# OSC_V1.net
KiCad netlist of a schematic drawn in EAGLE
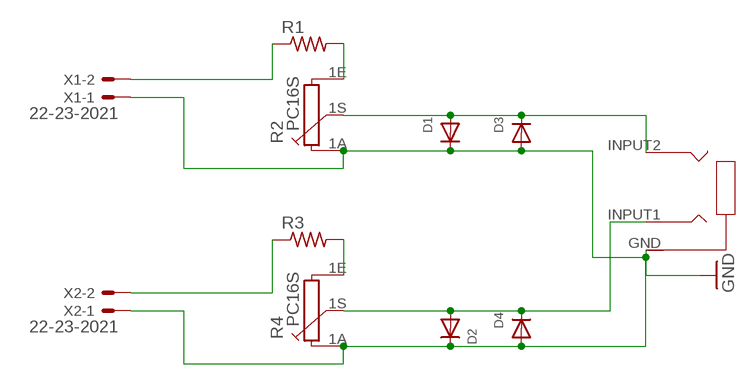
[diagram p0: schematic, sheet 1]

(export (version "E")
  (design (tool "Eeschema 10.0.6"))
  (components
    (comp (ref "D1")
      (value "DIODEDO-1N4148")
      (footprint "eagle-import:DO-1N4148")
      (fields (field (name "MPN") "1N4148 (DO-35)"))
      (libsource (lib "eagle-import") (part "DIODEDO-1N4148"))
    )
    (comp (ref "D2")
      (value "DIODEDO-1N4148")
      (footprint "eagle-import:DO-1N4148")
      (fields (field (name "MPN") "1N4148 (DO-35)"))
      (libsource (lib "eagle-import") (part "DIODEDO-1N4148"))
    )
    (comp (ref "D3")
      (value "DIODEDO-1N4148")
      (footprint "eagle-import:DO-1N4148")
      (fields (field (name "MPN") "1N4148 (DO-35)"))
      (libsource (lib "eagle-import") (part "DIODEDO-1N4148"))
    )
    (comp (ref "D4")
      (value "DIODEDO-1N4148")
      (footprint "eagle-import:DO-1N4148")
      (fields (field (name "MPN") "1N4148 (DO-35)"))
      (libsource (lib "eagle-import") (part "DIODEDO-1N4148"))
    )
    (comp (ref "R1")
      (value "R-US_0204/7")
      (footprint "eagle-import:0204_7")
      (libsource (lib "eagle-import") (part "R-US_0204/7"))
    )
    (comp (ref "R2")
      (value "PC16S")
      (footprint "eagle-import:PC16S")
      (fields (field (name "MPN") "P160KN-0QC15B500K") (field (name "OC_NEWARK") "14R5474"))
      (libsource (lib "eagle-import") (part "PC16S"))
    )
    (comp (ref "R3")
      (value "R-US_0204/7")
      (footprint "eagle-import:0204_7")
      (libsource (lib "eagle-import") (part "R-US_0204/7"))
    )
    (comp (ref "R4")
      (value "PC16S")
      (footprint "eagle-import:PC16S")
      (fields (field (name "MPN") "P160KN-0QC15B500K") (field (name "OC_NEWARK") "14R5474"))
      (libsource (lib "eagle-import") (part "PC16S"))
    )
    (comp (ref "U$1")
      (value "AUDIO3PIN")
      (footprint "eagle-import:AUDIO3PIN")
      (libsource (lib "eagle-import") (part "AUDIO3PIN"))
    )
    (comp (ref "X1")
      (value "22-23-2021")
      (footprint "eagle-import:22-23-2021")
      (fields (field (name "MF") "MOLEX") (field (name "OC_NEWARK") "unknown"))
      (libsource (lib "eagle-import") (part "22-23-2021"))
    )
    (comp (ref "X2")
      (value "22-23-2021")
      (footprint "eagle-import:22-23-2021")
      (fields (field (name "MF") "MOLEX") (field (name "OC_NEWARK") "unknown"))
      (libsource (lib "eagle-import") (part "22-23-2021"))
    )
  )
  (nets
    (net (code "1") (name "GND") (class "Default")
      (node (ref "D1") (pin "C") (pinfunction "C_C") (pintype "passive"))
      (node (ref "D2") (pin "C") (pinfunction "C_C") (pintype "passive"))
      (node (ref "D3") (pin "A") (pinfunction "A_A") (pintype "passive"))
      (node (ref "D4") (pin "A") (pinfunction "A_A") (pintype "passive"))
      (node (ref "R2") (pin "1A") (pinfunction "1A_1A") (pintype "passive"))
      (node (ref "R4") (pin "1A") (pinfunction "1A_1A") (pintype "passive"))
      (node (ref "U$1") (pin "GND") (pinfunction "GND_GND") (pintype "bidirectional"))
      (node (ref "X1") (pin "1") (pinfunction "S_1") (pintype "passive"))
      (node (ref "X2") (pin "1") (pinfunction "S_1") (pintype "passive"))
    )
    (net (code "2") (name "Net-(D1-PadA)") (class "Default")
      (node (ref "D1") (pin "A") (pinfunction "A_A") (pintype "passive"))
      (node (ref "D3") (pin "C") (pinfunction "C_C") (pintype "passive"))
      (node (ref "R2") (pin "1S") (pinfunction "1S_1S") (pintype "passive"))
      (node (ref "U$1") (pin "INPUT2") (pinfunction "INPUT2_INPUT2") (pintype "bidirectional"))
    )
    (net (code "3") (name "Net-(D2-PadA)") (class "Default")
      (node (ref "D2") (pin "A") (pinfunction "A_A") (pintype "passive"))
      (node (ref "D4") (pin "C") (pinfunction "C_C") (pintype "passive"))
      (node (ref "R4") (pin "1S") (pinfunction "1S_1S") (pintype "passive"))
      (node (ref "U$1") (pin "INPUT1") (pinfunction "INPUT1_INPUT1") (pintype "bidirectional"))
    )
    (net (code "4") (name "Net-(R1-Pad2)") (class "Default")
      (node (ref "R1") (pin "2") (pinfunction "2_2") (pintype "passive"))
      (node (ref "R2") (pin "1E") (pinfunction "1E_1E") (pintype "passive"))
    )
    (net (code "5") (name "Net-(R3-Pad2)") (class "Default")
      (node (ref "R3") (pin "2") (pinfunction "2_2") (pintype "passive"))
      (node (ref "R4") (pin "1E") (pinfunction "1E_1E") (pintype "passive"))
    )
    (net (code "6") (name "Net-(X1B-S)") (class "Default")
      (node (ref "R1") (pin "1") (pinfunction "1_1") (pintype "passive"))
      (node (ref "X1") (pin "2") (pinfunction "S_2") (pintype "passive"))
    )
    (net (code "7") (name "Net-(X2B-S)") (class "Default")
      (node (ref "R3") (pin "1") (pinfunction "1_1") (pintype "passive"))
      (node (ref "X2") (pin "2") (pinfunction "S_2") (pintype "passive"))
    )
  )
)
